# esptoy_v13.net
KiCad netlist of a schematic drawn in EAGLE
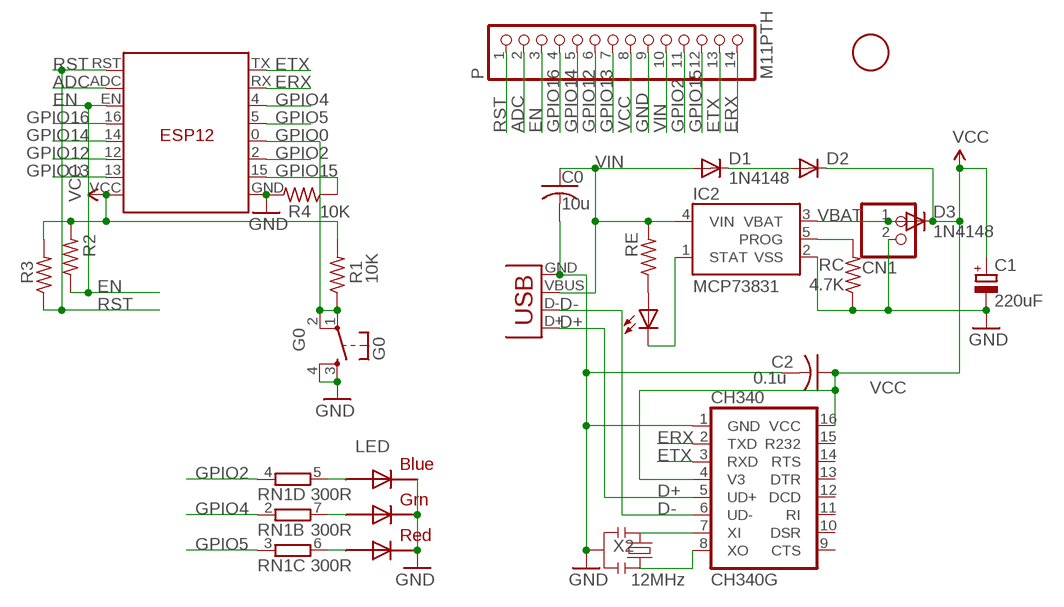
[diagram p0: schematic, sheet 1]

(export (version "E")
  (design (tool "Eeschema 10.0.6"))
  (components
    (comp (ref "1F")
      (value "FIDUCIAL")
      (footprint "eagle-import:FIDUCIAL_1MM")
      (libsource (lib "eagle-import") (part "FIDUCIAL"))
    )
    (comp (ref "C0")
      (value "10u")
      (footprint "eagle-import:C0805K")
      (libsource (lib "eagle-import") (part "adafruit2013_C-USC0805K"))
    )
    (comp (ref "C1")
      (value "220uF")
      (footprint "eagle-import:CT3528")
      (libsource (lib "eagle-import") (part "CPOL-EUCT3528"))
    )
    (comp (ref "C2")
      (value "0.1u")
      (footprint "eagle-import:C0603K")
      (libsource (lib "eagle-import") (part "C-USC0603K"))
    )
    (comp (ref "CH340")
      (value "CH340G")
      (footprint "eagle-import:SO16")
      (libsource (lib "eagle-import") (part "CH340G"))
    )
    (comp (ref "CHG")
      (value "0805")
      (footprint "eagle-import:CHIPLED_0805")
      (libsource (lib "eagle-import") (part "LEDCHIPLED_0805"))
    )
    (comp (ref "CN1")
      (value "JST_2PIN-SMT-RA")
      (footprint "eagle-import:JST-PH-2-SMT-RA")
      (libsource (lib "eagle-import") (part "JST_2PIN-SMT-RA"))
    )
    (comp (ref "D1")
      (value "1N4148")
      (footprint "eagle-import:DO-214AC")
      (libsource (lib "eagle-import") (part "DIODE-DO-214AC"))
    )
    (comp (ref "D2")
      (value "DIODE-DO-214AC")
      (footprint "eagle-import:DO-214AC")
      (libsource (lib "eagle-import") (part "DIODE-DO-214AC"))
    )
    (comp (ref "D3")
      (value "1N4148")
      (footprint "eagle-import:DO-214AC")
      (libsource (lib "eagle-import") (part "DIODE-DO-214AC"))
    )
    (comp (ref "G0")
      (value "G0")
      (footprint "eagle-import:TACTILE_SWITCH_SMD")
      (libsource (lib "eagle-import") (part "TAC_SWITCHSMD"))
    )
    (comp (ref "IC2")
      (value "MCP73831")
      (footprint "eagle-import:SOT23-5")
      (libsource (lib "eagle-import") (part "MCP73831"))
    )
    (comp (ref "LED")
      (value "RGBLED5050")
      (footprint "eagle-import:RGBLED5050")
      (libsource (lib "eagle-import") (part "RGBLED5050"))
    )
    (comp (ref "P")
      (value "M11PTH")
      (footprint "eagle-import:1X14-CB")
      (libsource (lib "eagle-import") (part "PINHD-1X14-CB"))
    )
    (comp (ref "R1")
      (value "10K")
      (footprint "eagle-import:R0603")
      (libsource (lib "eagle-import") (part "R-US_R0603"))
    )
    (comp (ref "R2")
      (value "R-US_R0603")
      (footprint "eagle-import:R0603")
      (libsource (lib "eagle-import") (part "R-US_R0603"))
    )
    (comp (ref "R3")
      (value "R-US_R0603")
      (footprint "eagle-import:R0603")
      (libsource (lib "eagle-import") (part "R-US_R0603"))
    )
    (comp (ref "R4")
      (value "10K")
      (footprint "eagle-import:R0603")
      (libsource (lib "eagle-import") (part "R-US_R0603"))
    )
    (comp (ref "RC")
      (value "4.7K")
      (footprint "eagle-import:R0603")
      (libsource (lib "eagle-import") (part "adafruit2013_R-US_R0603"))
    )
    (comp (ref "RE")
      (value "R-US_R0603")
      (footprint "eagle-import:R0603")
      (libsource (lib "eagle-import") (part "R-US_R0603"))
    )
    (comp (ref "RN1")
      (value "300R")
      (footprint "eagle-import:EXB38V")
      (libsource (lib "eagle-import") (part "4R-NEXB38V"))
    )
    (comp (ref "U$1")
      (value "ESP12")
      (footprint "eagle-import:ESP12")
      (libsource (lib "eagle-import") (part "ESP12"))
    )
    (comp (ref "X2")
      (value "12MHz")
      (footprint "eagle-import:RESONATOR-SMD")
      (libsource (lib "eagle-import") (part "RESONATORSMD"))
    )
    (comp (ref "X3")
      (value "USBMICROB2")
      (footprint "eagle-import:USB-MICROB2")
      (libsource (lib "eagle-import") (part "USBMICROB2"))
    )
  )
  (nets
    (net (code "1") (name "/ADC") (class "Default")
      (node (ref "P") (pin "2") (pinfunction "2_2") (pintype "passive"))
      (node (ref "U$1") (pin "ADC") (pinfunction "ADC_ADC") (pintype "bidirectional"))
    )
    (net (code "2") (name "/D+") (class "Default")
      (node (ref "CH340") (pin "5") (pinfunction "UD+_5") (pintype "bidirectional"))
      (node (ref "X3") (pin "D+") (pinfunction "D+_D+") (pintype "bidirectional"))
    )
    (net (code "3") (name "/D-") (class "Default")
      (node (ref "CH340") (pin "6") (pinfunction "UD-_6") (pintype "bidirectional"))
      (node (ref "X3") (pin "D-") (pinfunction "D-_D-") (pintype "bidirectional"))
    )
    (net (code "4") (name "/EN") (class "Default")
      (node (ref "P") (pin "3") (pinfunction "3_3") (pintype "passive"))
      (node (ref "R2") (pin "1") (pinfunction "1_1") (pintype "passive"))
      (node (ref "U$1") (pin "EN") (pinfunction "EN_EN") (pintype "bidirectional"))
    )
    (net (code "5") (name "/ERX") (class "Default")
      (node (ref "CH340") (pin "2") (pinfunction "TXD_2") (pintype "bidirectional"))
      (node (ref "P") (pin "14") (pinfunction "14_14") (pintype "passive"))
      (node (ref "U$1") (pin "RX") (pinfunction "RX_RX") (pintype "bidirectional"))
    )
    (net (code "6") (name "/ETX") (class "Default")
      (node (ref "CH340") (pin "3") (pinfunction "RXD_3") (pintype "bidirectional"))
      (node (ref "P") (pin "13") (pinfunction "13_13") (pintype "passive"))
      (node (ref "U$1") (pin "TX") (pinfunction "TX_TX") (pintype "bidirectional"))
    )
    (net (code "7") (name "/GPIO0") (class "Default")
      (node (ref "G0") (pin "1") (pinfunction "1_1") (pintype "passive"))
      (node (ref "G0") (pin "2") (pinfunction "2_2") (pintype "passive"))
      (node (ref "R1") (pin "1") (pinfunction "1_1") (pintype "passive"))
      (node (ref "U$1") (pin "0") (pinfunction "G0_0") (pintype "bidirectional"))
    )
    (net (code "8") (name "/GPIO2") (class "Default")
      (node (ref "P") (pin "11") (pinfunction "11_11") (pintype "passive"))
      (node (ref "RN1") (pin "4") (pinfunction "1_4") (pintype "passive"))
      (node (ref "U$1") (pin "2") (pinfunction "G2_2") (pintype "bidirectional"))
    )
    (net (code "9") (name "/GPIO4") (class "Default")
      (node (ref "RN1") (pin "2") (pinfunction "1_2") (pintype "passive"))
      (node (ref "U$1") (pin "4") (pinfunction "G4_4") (pintype "bidirectional"))
    )
    (net (code "10") (name "/GPIO5") (class "Default")
      (node (ref "RN1") (pin "3") (pinfunction "1_3") (pintype "passive"))
      (node (ref "U$1") (pin "5") (pinfunction "G5_5") (pintype "bidirectional"))
    )
    (net (code "11") (name "/GPIO12") (class "Default")
      (node (ref "P") (pin "6") (pinfunction "6_6") (pintype "passive"))
      (node (ref "U$1") (pin "12") (pinfunction "G12_12") (pintype "bidirectional"))
    )
    (net (code "12") (name "/GPIO13") (class "Default")
      (node (ref "P") (pin "7") (pinfunction "7_7") (pintype "passive"))
      (node (ref "U$1") (pin "13") (pinfunction "G13_13") (pintype "bidirectional"))
    )
    (net (code "13") (name "/GPIO14") (class "Default")
      (node (ref "P") (pin "5") (pinfunction "5_5") (pintype "passive"))
      (node (ref "U$1") (pin "14") (pinfunction "G14_14") (pintype "bidirectional"))
    )
    (net (code "14") (name "/GPIO15") (class "Default")
      (node (ref "P") (pin "12") (pinfunction "12_12") (pintype "passive"))
      (node (ref "R4") (pin "1") (pinfunction "1_1") (pintype "passive"))
      (node (ref "U$1") (pin "15") (pinfunction "G15_15") (pintype "bidirectional"))
    )
    (net (code "15") (name "/GPIO16") (class "Default")
      (node (ref "P") (pin "4") (pinfunction "4_4") (pintype "passive"))
      (node (ref "U$1") (pin "16") (pinfunction "G16_16") (pintype "bidirectional"))
    )
    (net (code "16") (name "/RST") (class "Default")
      (node (ref "P") (pin "1") (pinfunction "1_1") (pintype "passive"))
      (node (ref "R3") (pin "1") (pinfunction "1_1") (pintype "passive"))
      (node (ref "U$1") (pin "RST") (pinfunction "RST_RST") (pintype "bidirectional"))
    )
    (net (code "17") (name "/VBAT") (class "Default")
      (node (ref "CN1") (pin "1") (pinfunction "2_1") (pintype "passive"))
      (node (ref "D3") (pin "A") (pinfunction "A_A") (pintype "passive"))
      (node (ref "IC2") (pin "3") (pinfunction "VBAT_3") (pintype "power_in"))
    )
    (net (code "18") (name "/VIN") (class "Default")
      (node (ref "C0") (pin "1") (pinfunction "1_1") (pintype "passive"))
      (node (ref "D1") (pin "A") (pinfunction "A_A") (pintype "passive"))
      (node (ref "IC2") (pin "4") (pinfunction "VIN_4") (pintype "power_in"))
      (node (ref "P") (pin "10") (pinfunction "10_10") (pintype "passive"))
      (node (ref "RE") (pin "2") (pinfunction "2_2") (pintype "passive"))
      (node (ref "X3") (pin "VBUS") (pinfunction "VBUS_VBUS") (pintype "bidirectional"))
    )
    (net (code "19") (name "GND") (class "Default")
      (node (ref "C0") (pin "2") (pinfunction "2_2") (pintype "passive"))
      (node (ref "C1") (pin "-") (pinfunction "-_-") (pintype "passive"))
      (node (ref "C2") (pin "2") (pinfunction "2_2") (pintype "passive"))
      (node (ref "CH340") (pin "1") (pinfunction "GND_1") (pintype "power_in"))
      (node (ref "CN1") (pin "2") (pinfunction "1_2") (pintype "passive"))
      (node (ref "G0") (pin "3") (pinfunction "3_3") (pintype "passive"))
      (node (ref "G0") (pin "4") (pinfunction "4_4") (pintype "passive"))
      (node (ref "IC2") (pin "2") (pinfunction "VSS_2") (pintype "power_in"))
      (node (ref "LED") (pin "4") (pinfunction "BLUE_C_4") (pintype "bidirectional"))
      (node (ref "LED") (pin "5") (pinfunction "RED_C_5") (pintype "bidirectional"))
      (node (ref "LED") (pin "6") (pinfunction "GREEN_C_6") (pintype "bidirectional"))
      (node (ref "P") (pin "9") (pinfunction "9_9") (pintype "passive"))
      (node (ref "R4") (pin "2") (pinfunction "2_2") (pintype "passive"))
      (node (ref "RC") (pin "1") (pinfunction "1_1") (pintype "passive"))
      (node (ref "U$1") (pin "GND") (pinfunction "GND_GND") (pintype "power_in"))
      (node (ref "X2") (pin "2") (pinfunction "2_2") (pintype "passive"))
      (node (ref "X3") (pin "GND") (pinfunction "GND_GND") (pintype "bidirectional"))
    )
    (net (code "20") (name "Net-(CH340-XI)") (class "Default")
      (node (ref "CH340") (pin "7") (pinfunction "XI_7") (pintype "bidirectional"))
      (node (ref "X2") (pin "1") (pinfunction "1_1") (pintype "passive"))
    )
    (net (code "21") (name "Net-(CH340-XO)") (class "Default")
      (node (ref "CH340") (pin "8") (pinfunction "XO_8") (pintype "bidirectional"))
      (node (ref "X2") (pin "3") (pinfunction "3_3") (pintype "passive"))
    )
    (net (code "22") (name "Net-(CHG-PadA)") (class "Default")
      (node (ref "CHG") (pin "A") (pinfunction "A_A") (pintype "passive"))
      (node (ref "RE") (pin "1") (pinfunction "1_1") (pintype "passive"))
    )
    (net (code "23") (name "Net-(D1-PadC)") (class "Default")
      (node (ref "D1") (pin "C") (pinfunction "C_C") (pintype "passive"))
      (node (ref "D2") (pin "A") (pinfunction "A_A") (pintype "passive"))
    )
    (net (code "24") (name "Net-(IC2-PROG)") (class "Default")
      (node (ref "IC2") (pin "5") (pinfunction "PROG_5") (pintype "input"))
      (node (ref "RC") (pin "2") (pinfunction "2_2") (pintype "passive"))
    )
    (net (code "25") (name "Net-(IC2-STAT)") (class "Default")
      (node (ref "CHG") (pin "C") (pinfunction "C_C") (pintype "passive"))
      (node (ref "IC2") (pin "1") (pinfunction "STAT_1") (pintype "output"))
    )
    (net (code "26") (name "Net-(LED-BLUE_A)") (class "Default")
      (node (ref "LED") (pin "3") (pinfunction "BLUE_A_3") (pintype "bidirectional"))
      (node (ref "RN1") (pin "5") (pinfunction "2_5") (pintype "passive"))
    )
    (net (code "27") (name "Net-(LED-GREEN_A)") (class "Default")
      (node (ref "LED") (pin "1") (pinfunction "GREEN_A_1") (pintype "bidirectional"))
      (node (ref "RN1") (pin "7") (pinfunction "2_7") (pintype "passive"))
    )
    (net (code "28") (name "Net-(LED-RED_A)") (class "Default")
      (node (ref "LED") (pin "2") (pinfunction "RED_A_2") (pintype "bidirectional"))
      (node (ref "RN1") (pin "6") (pinfunction "2_6") (pintype "passive"))
    )
    (net (code "29") (name "VCC") (class "Default")
      (node (ref "C1") (pin "+") (pinfunction "+_+") (pintype "passive"))
      (node (ref "C2") (pin "1") (pinfunction "1_1") (pintype "passive"))
      (node (ref "CH340") (pin "16") (pinfunction "VCC_16") (pintype "power_in"))
      (node (ref "CH340") (pin "4") (pinfunction "V3_4") (pintype "bidirectional"))
      (node (ref "D2") (pin "C") (pinfunction "C_C") (pintype "passive"))
      (node (ref "D3") (pin "C") (pinfunction "C_C") (pintype "passive"))
      (node (ref "P") (pin "8") (pinfunction "8_8") (pintype "passive"))
      (node (ref "R1") (pin "2") (pinfunction "2_2") (pintype "passive"))
      (node (ref "R2") (pin "2") (pinfunction "2_2") (pintype "passive"))
      (node (ref "R3") (pin "2") (pinfunction "2_2") (pintype "passive"))
      (node (ref "U$1") (pin "VCC") (pinfunction "VCC_VCC") (pintype "power_in"))
    )
    (net (code "30") (name "unconnected-(CH340-CTS-Pad9)") (class "Default")
      (node (ref "CH340") (pin "9") (pinfunction "CTS_9") (pintype "bidirectional"))
    )
    (net (code "31") (name "unconnected-(CH340-DCD-Pad12)") (class "Default")
      (node (ref "CH340") (pin "12") (pinfunction "DCD_12") (pintype "bidirectional"))
    )
    (net (code "32") (name "unconnected-(CH340-DSR-Pad10)") (class "Default")
      (node (ref "CH340") (pin "10") (pinfunction "DSR_10") (pintype "bidirectional"))
    )
    (net (code "33") (name "unconnected-(CH340-DTR-Pad13)") (class "Default")
      (node (ref "CH340") (pin "13") (pinfunction "DTR_13") (pintype "bidirectional"))
    )
    (net (code "34") (name "unconnected-(CH340-R232-Pad15)") (class "Default")
      (node (ref "CH340") (pin "15") (pinfunction "R232_15") (pintype "bidirectional"))
    )
    (net (code "35") (name "unconnected-(CH340-RI-Pad11)") (class "Default")
      (node (ref "CH340") (pin "11") (pinfunction "RI_11") (pintype "bidirectional"))
    )
    (net (code "36") (name "unconnected-(CH340-RTS-Pad14)") (class "Default")
      (node (ref "CH340") (pin "14") (pinfunction "RTS_14") (pintype "bidirectional"))
    )
  )
)
